# lattice-isp.net
KiCad netlist of a schematic drawn in EAGLE
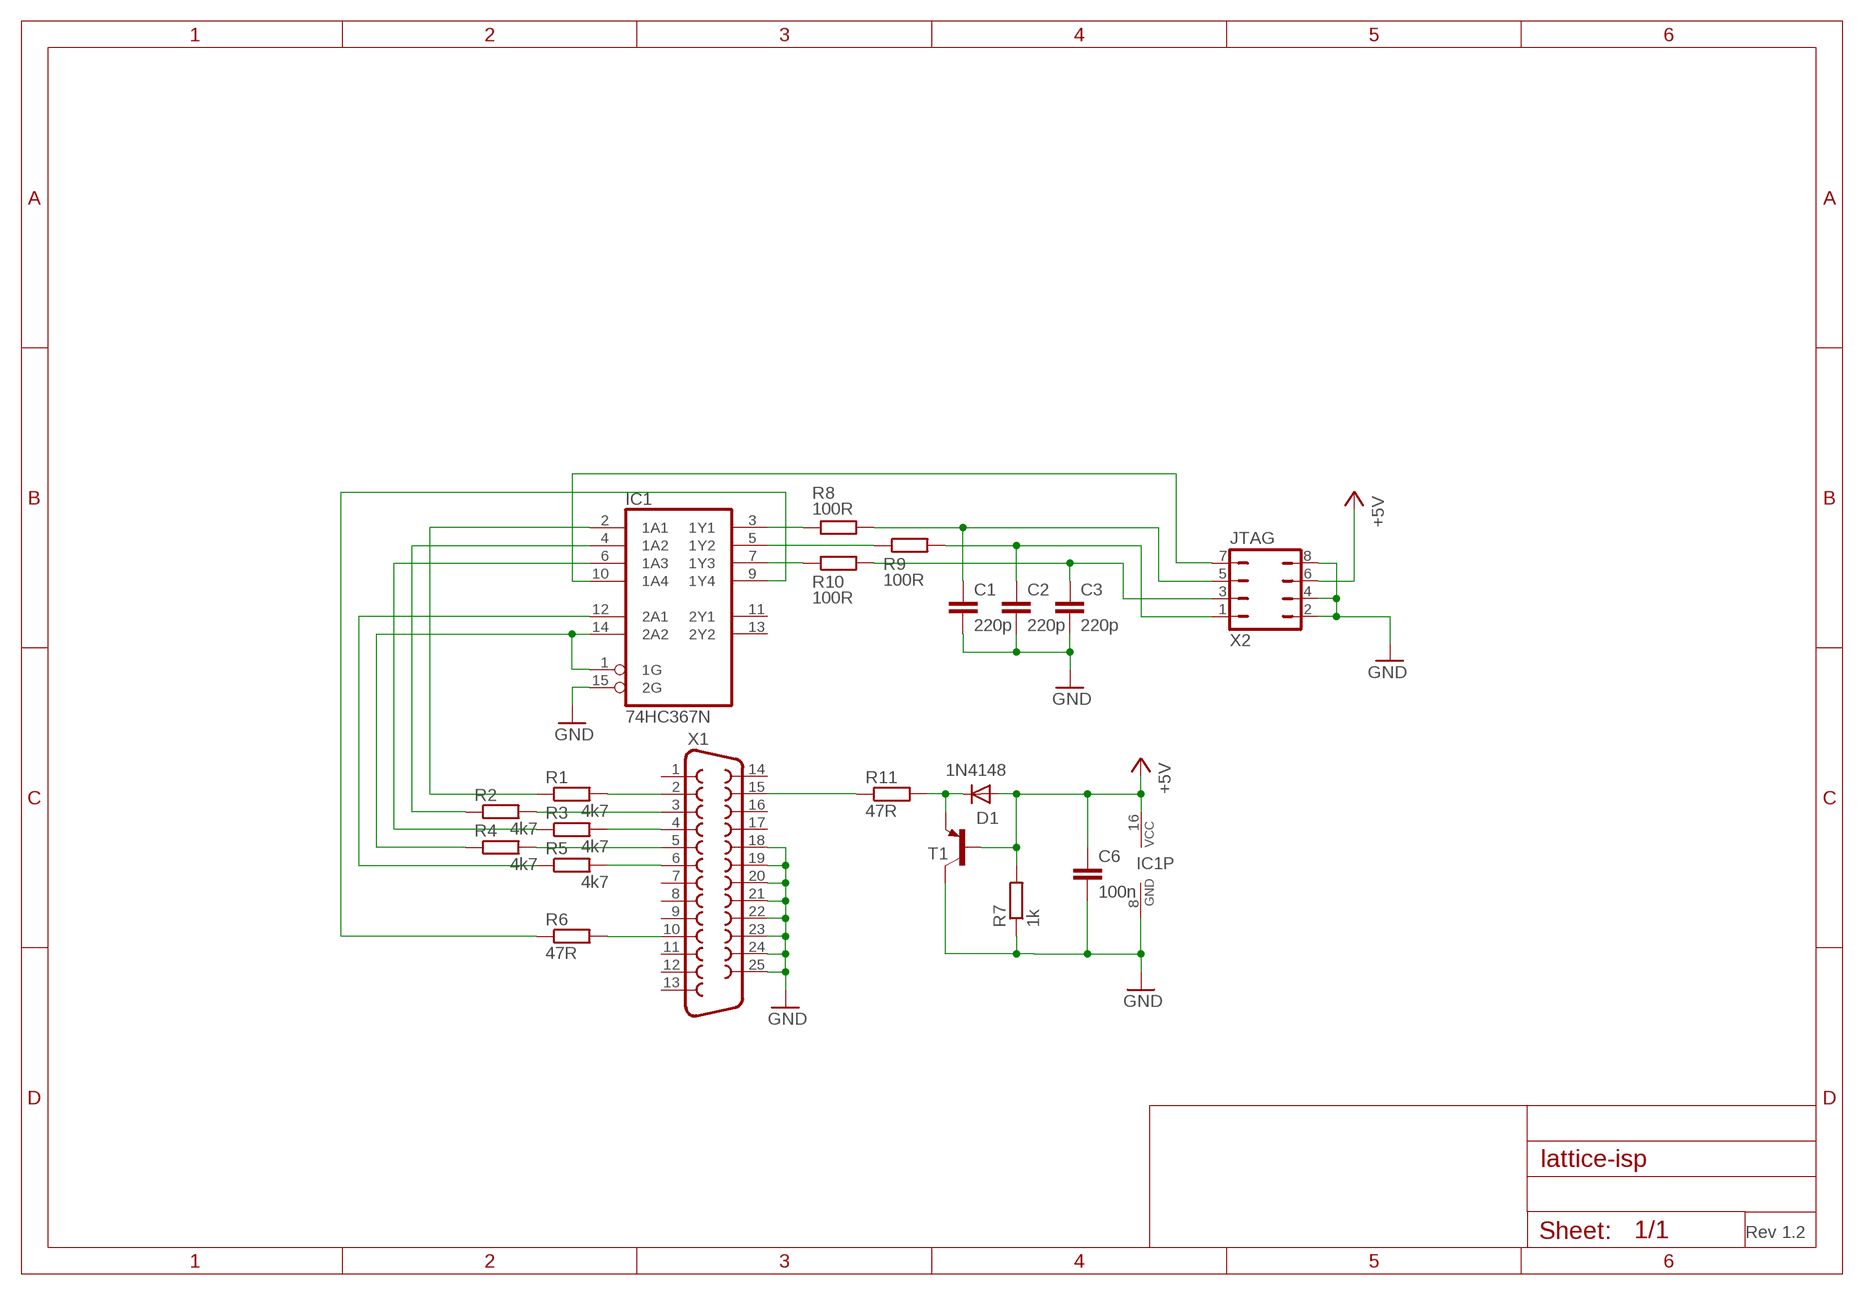
[diagram p0: schematic, sheet 1]

(export (version "E")
  (design (tool "Eeschema 10.0.6"))
  (components
    (comp (ref "C1")
      (value "220p")
      (footprint "eagle-import:C025-024X044")
      (libsource (lib "eagle-import") (part "C-EU025-024X044"))
    )
    (comp (ref "C2")
      (value "220p")
      (footprint "eagle-import:C025-024X044")
      (libsource (lib "eagle-import") (part "C-EU025-024X044"))
    )
    (comp (ref "C3")
      (value "220p")
      (footprint "eagle-import:C025-024X044")
      (libsource (lib "eagle-import") (part "C-EU025-024X044"))
    )
    (comp (ref "C6")
      (value "100n")
      (footprint "eagle-import:C050-024X044")
      (libsource (lib "eagle-import") (part "C-EU050-024X044"))
    )
    (comp (ref "D1")
      (value "1N4148")
      (footprint "eagle-import:DO35-7")
      (libsource (lib "eagle-import") (part "1N4148DO35-7"))
    )
    (comp (ref "IC1")
      (value "74HC367N")
      (footprint "eagle-import:DIL16")
      (libsource (lib "eagle-import") (part "74367NHC"))
    )
    (comp (ref "R1")
      (value "4k7")
      (footprint "eagle-import:0207_10")
      (libsource (lib "eagle-import") (part "R-EU_0207/10"))
    )
    (comp (ref "R2")
      (value "4k7")
      (footprint "eagle-import:0207_10")
      (libsource (lib "eagle-import") (part "R-EU_0207/10"))
    )
    (comp (ref "R3")
      (value "4k7")
      (footprint "eagle-import:0207_10")
      (libsource (lib "eagle-import") (part "R-EU_0207/10"))
    )
    (comp (ref "R4")
      (value "4k7")
      (footprint "eagle-import:0207_10")
      (libsource (lib "eagle-import") (part "R-EU_0207/10"))
    )
    (comp (ref "R5")
      (value "4k7")
      (footprint "eagle-import:0207_10")
      (libsource (lib "eagle-import") (part "R-EU_0207/10"))
    )
    (comp (ref "R6")
      (value "47R")
      (footprint "eagle-import:0207_10")
      (libsource (lib "eagle-import") (part "R-EU_0207/10"))
    )
    (comp (ref "R7")
      (value "1k")
      (footprint "eagle-import:0207_10")
      (libsource (lib "eagle-import") (part "R-EU_0207/10"))
    )
    (comp (ref "R8")
      (value "100R")
      (footprint "eagle-import:0207_10")
      (libsource (lib "eagle-import") (part "R-EU_0207/10"))
    )
    (comp (ref "R9")
      (value "100R")
      (footprint "eagle-import:0207_10")
      (libsource (lib "eagle-import") (part "R-EU_0207/10"))
    )
    (comp (ref "R10")
      (value "100R")
      (footprint "eagle-import:0207_10")
      (libsource (lib "eagle-import") (part "R-EU_0207/10"))
    )
    (comp (ref "R11")
      (value "47R")
      (footprint "eagle-import:0207_10")
      (libsource (lib "eagle-import") (part "R-EU_0207/10"))
    )
    (comp (ref "T1")
      (value "BC636-PNP-TO92-BCE")
      (footprint "eagle-import:TO92-BCE")
      (libsource (lib "eagle-import") (part "-PNP-TO92-BCEBC636"))
    )
    (comp (ref "X1")
      (value "F25HP")
      (footprint "eagle-import:F25HP")
      (libsource (lib "eagle-import") (part "F25HP"))
    )
    (comp (ref "X2")
      (value "JTAG")
      (footprint "eagle-import:JP4Q")
      (libsource (lib "eagle-import") (part "JP4Q"))
    )
  )
  (nets
    (net (code "1") (name "+5V") (class "Default")
      (node (ref "C6") (pin "1") (pinfunction "1_1") (pintype "passive"))
      (node (ref "D1") (pin "A") (pinfunction "A_A") (pintype "passive"))
      (node (ref "IC1") (pin "16") (pinfunction "VCC_16") (pintype "power_in"))
      (node (ref "R7") (pin "2") (pinfunction "2_2") (pintype "passive"))
      (node (ref "T1") (pin "B") (pinfunction "B_B") (pintype "passive"))
      (node (ref "X2") (pin "6") (pinfunction "6_6") (pintype "passive"))
    )
    (net (code "2") (name "GND") (class "Default")
      (node (ref "C1") (pin "2") (pinfunction "2_2") (pintype "passive"))
      (node (ref "C2") (pin "2") (pinfunction "2_2") (pintype "passive"))
      (node (ref "C3") (pin "2") (pinfunction "2_2") (pintype "passive"))
      (node (ref "C6") (pin "2") (pinfunction "2_2") (pintype "passive"))
      (node (ref "IC1") (pin "15") (pinfunction "2G_15") (pintype "input"))
      (node (ref "IC1") (pin "8") (pinfunction "GND_8") (pintype "power_in"))
      (node (ref "R7") (pin "1") (pinfunction "1_1") (pintype "passive"))
      (node (ref "T1") (pin "C") (pinfunction "C_C") (pintype "passive"))
      (node (ref "X1") (pin "18") (pinfunction "18_18") (pintype "passive"))
      (node (ref "X1") (pin "19") (pinfunction "19_19") (pintype "passive"))
      (node (ref "X1") (pin "20") (pinfunction "20_20") (pintype "passive"))
      (node (ref "X1") (pin "21") (pinfunction "21_21") (pintype "passive"))
      (node (ref "X1") (pin "22") (pinfunction "22_22") (pintype "passive"))
      (node (ref "X1") (pin "23") (pinfunction "23_23") (pintype "passive"))
      (node (ref "X1") (pin "24") (pinfunction "24_24") (pintype "passive"))
      (node (ref "X1") (pin "25") (pinfunction "25_25") (pintype "passive"))
      (node (ref "X2") (pin "2") (pinfunction "2_2") (pintype "passive"))
      (node (ref "X2") (pin "4") (pinfunction "4_4") (pintype "passive"))
      (node (ref "X2") (pin "8") (pinfunction "8_8") (pintype "passive"))
    )
    (net (code "3") (name "Net-(C1-Pad1)") (class "Default")
      (node (ref "C1") (pin "1") (pinfunction "1_1") (pintype "passive"))
      (node (ref "R8") (pin "2") (pinfunction "2_2") (pintype "passive"))
      (node (ref "X2") (pin "5") (pinfunction "5_5") (pintype "passive"))
    )
    (net (code "4") (name "Net-(C2-Pad1)") (class "Default")
      (node (ref "C2") (pin "1") (pinfunction "1_1") (pintype "passive"))
      (node (ref "R9") (pin "2") (pinfunction "2_2") (pintype "passive"))
      (node (ref "X2") (pin "1") (pinfunction "1_1") (pintype "passive"))
    )
    (net (code "5") (name "Net-(C3-Pad1)") (class "Default")
      (node (ref "C3") (pin "1") (pinfunction "1_1") (pintype "passive"))
      (node (ref "R10") (pin "2") (pinfunction "2_2") (pintype "passive"))
      (node (ref "X2") (pin "3") (pinfunction "3_3") (pintype "passive"))
    )
    (net (code "6") (name "Net-(D1-PadC)") (class "Default")
      (node (ref "D1") (pin "C") (pinfunction "C_C") (pintype "passive"))
      (node (ref "R11") (pin "2") (pinfunction "2_2") (pintype "passive"))
      (node (ref "T1") (pin "E") (pinfunction "E_E") (pintype "passive"))
    )
    (net (code "7") (name "Net-(IC1A-1A1)") (class "Default")
      (node (ref "IC1") (pin "2") (pinfunction "1A1_2") (pintype "input"))
      (node (ref "R1") (pin "1") (pinfunction "1_1") (pintype "passive"))
    )
    (net (code "8") (name "Net-(IC1A-1A2)") (class "Default")
      (node (ref "IC1") (pin "4") (pinfunction "1A2_4") (pintype "input"))
      (node (ref "R2") (pin "1") (pinfunction "1_1") (pintype "passive"))
    )
    (net (code "9") (name "Net-(IC1A-1A3)") (class "Default")
      (node (ref "IC1") (pin "6") (pinfunction "1A3_6") (pintype "input"))
      (node (ref "R3") (pin "1") (pinfunction "1_1") (pintype "passive"))
    )
    (net (code "10") (name "Net-(IC1A-1A4)") (class "Default")
      (node (ref "IC1") (pin "10") (pinfunction "1A4_10") (pintype "input"))
      (node (ref "X2") (pin "7") (pinfunction "7_7") (pintype "passive"))
    )
    (net (code "11") (name "Net-(IC1A-1G)") (class "Default")
      (node (ref "IC1") (pin "1") (pinfunction "1G_1") (pintype "input"))
      (node (ref "IC1") (pin "14") (pinfunction "2A2_14") (pintype "input"))
      (node (ref "R4") (pin "1") (pinfunction "1_1") (pintype "passive"))
    )
    (net (code "12") (name "Net-(IC1A-1Y1)") (class "Default")
      (node (ref "IC1") (pin "3") (pinfunction "1Y1_3") (pintype "tri_state"))
      (node (ref "R8") (pin "1") (pinfunction "1_1") (pintype "passive"))
    )
    (net (code "13") (name "Net-(IC1A-1Y2)") (class "Default")
      (node (ref "IC1") (pin "5") (pinfunction "1Y2_5") (pintype "tri_state"))
      (node (ref "R9") (pin "1") (pinfunction "1_1") (pintype "passive"))
    )
    (net (code "14") (name "Net-(IC1A-1Y3)") (class "Default")
      (node (ref "IC1") (pin "7") (pinfunction "1Y3_7") (pintype "tri_state"))
      (node (ref "R10") (pin "1") (pinfunction "1_1") (pintype "passive"))
    )
    (net (code "15") (name "Net-(IC1A-1Y4)") (class "Default")
      (node (ref "IC1") (pin "9") (pinfunction "1Y4_9") (pintype "tri_state"))
      (node (ref "R6") (pin "1") (pinfunction "1_1") (pintype "passive"))
    )
    (net (code "16") (name "Net-(IC1A-2A1)") (class "Default")
      (node (ref "IC1") (pin "12") (pinfunction "2A1_12") (pintype "input"))
      (node (ref "R5") (pin "1") (pinfunction "1_1") (pintype "passive"))
    )
    (net (code "17") (name "Net-(R1-Pad2)") (class "Default")
      (node (ref "R1") (pin "2") (pinfunction "2_2") (pintype "passive"))
      (node (ref "X1") (pin "2") (pinfunction "2_2") (pintype "passive"))
    )
    (net (code "18") (name "Net-(R2-Pad2)") (class "Default")
      (node (ref "R2") (pin "2") (pinfunction "2_2") (pintype "passive"))
      (node (ref "X1") (pin "3") (pinfunction "3_3") (pintype "passive"))
    )
    (net (code "19") (name "Net-(R3-Pad2)") (class "Default")
      (node (ref "R3") (pin "2") (pinfunction "2_2") (pintype "passive"))
      (node (ref "X1") (pin "4") (pinfunction "4_4") (pintype "passive"))
    )
    (net (code "20") (name "Net-(R4-Pad2)") (class "Default")
      (node (ref "R4") (pin "2") (pinfunction "2_2") (pintype "passive"))
      (node (ref "X1") (pin "5") (pinfunction "5_5") (pintype "passive"))
    )
    (net (code "21") (name "Net-(R5-Pad2)") (class "Default")
      (node (ref "R5") (pin "2") (pinfunction "2_2") (pintype "passive"))
      (node (ref "X1") (pin "6") (pinfunction "6_6") (pintype "passive"))
    )
    (net (code "22") (name "Net-(R6-Pad2)") (class "Default")
      (node (ref "R6") (pin "2") (pinfunction "2_2") (pintype "passive"))
      (node (ref "X1") (pin "10") (pinfunction "10_10") (pintype "passive"))
    )
    (net (code "23") (name "Net-(R11-Pad1)") (class "Default")
      (node (ref "R11") (pin "1") (pinfunction "1_1") (pintype "passive"))
      (node (ref "X1") (pin "15") (pinfunction "15_15") (pintype "passive"))
    )
    (net (code "24") (name "unconnected-(IC1A-2Y1-Pad11)") (class "Default")
      (node (ref "IC1") (pin "11") (pinfunction "2Y1_11") (pintype "tri_state"))
    )
    (net (code "25") (name "unconnected-(IC1A-2Y2-Pad13)") (class "Default")
      (node (ref "IC1") (pin "13") (pinfunction "2Y2_13") (pintype "tri_state"))
    )
    (net (code "26") (name "unconnected-(X1-Pad1)") (class "Default")
      (node (ref "X1") (pin "1") (pinfunction "1_1") (pintype "passive"))
    )
    (net (code "27") (name "unconnected-(X1-Pad7)") (class "Default")
      (node (ref "X1") (pin "7") (pinfunction "7_7") (pintype "passive"))
    )
    (net (code "28") (name "unconnected-(X1-Pad8)") (class "Default")
      (node (ref "X1") (pin "8") (pinfunction "8_8") (pintype "passive"))
    )
    (net (code "29") (name "unconnected-(X1-Pad9)") (class "Default")
      (node (ref "X1") (pin "9") (pinfunction "9_9") (pintype "passive"))
    )
    (net (code "30") (name "unconnected-(X1-Pad11)") (class "Default")
      (node (ref "X1") (pin "11") (pinfunction "11_11") (pintype "passive"))
    )
    (net (code "31") (name "unconnected-(X1-Pad12)") (class "Default")
      (node (ref "X1") (pin "12") (pinfunction "12_12") (pintype "passive"))
    )
    (net (code "32") (name "unconnected-(X1-Pad13)") (class "Default")
      (node (ref "X1") (pin "13") (pinfunction "13_13") (pintype "passive"))
    )
    (net (code "33") (name "unconnected-(X1-Pad14)") (class "Default")
      (node (ref "X1") (pin "14") (pinfunction "14_14") (pintype "passive"))
    )
    (net (code "34") (name "unconnected-(X1-Pad16)") (class "Default")
      (node (ref "X1") (pin "16") (pinfunction "16_16") (pintype "passive"))
    )
    (net (code "35") (name "unconnected-(X1-Pad17)") (class "Default")
      (node (ref "X1") (pin "17") (pinfunction "17_17") (pintype "passive"))
    )
  )
)
